# AerO2_Sheet1.net
KiCad netlist of a schematic drawn in Altium Designer
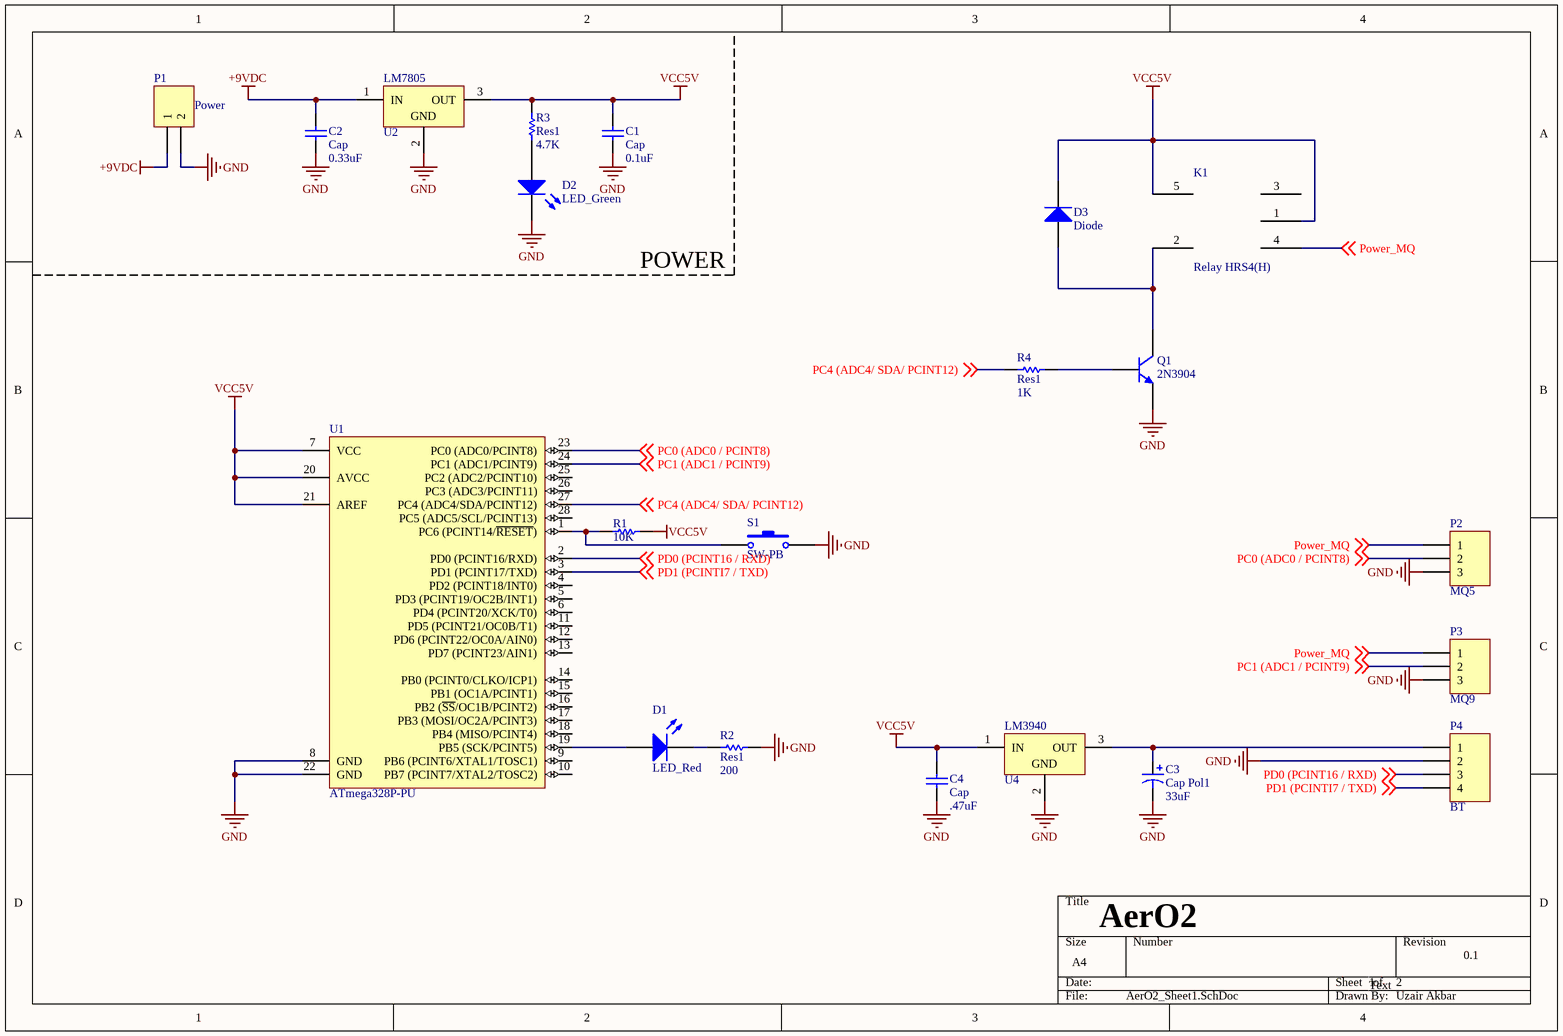
[diagram p0: AerO2_Sheet1.SchDoc]

(export (version "E")
  (design (tool "Eeschema 10.0.6"))
  (components
    (comp (ref "C1")
      (value "Cap")
      (footprint "RAD-0.1")
      (description "Capacitor")
      (fields (field (name "ALTIUM_VALUE") "0.1uF") (field (name "PUBLISHER") "Altium Limited"))
      (libsource (lib "Miscellaneous Devices") (part "Cap"))
    )
    (comp (ref "C2")
      (value "Cap")
      (footprint "RAD-0.1")
      (description "Capacitor")
      (fields (field (name "ALTIUM_VALUE") "0.33uF") (field (name "PUBLISHER") "Altium Limited"))
      (libsource (lib "Miscellaneous Devices") (part "Cap"))
    )
    (comp (ref "C3")
      (value "Cap Pol1")
      (footprint "RB5-10.5")
      (description "Polarized Capacitor (Radial)")
      (fields (field (name "ALTIUM_VALUE") "33uF") (field (name "PUBLISHER") "Altium Limited"))
      (libsource (lib "Miscellaneous Devices") (part "Cap Pol1"))
    )
    (comp (ref "C4")
      (value "Cap")
      (footprint "RAD-0.1")
      (description "Capacitor")
      (fields (field (name "ALTIUM_VALUE") ".47uF") (field (name "PUBLISHER") "Altium Limited"))
      (libsource (lib "Miscellaneous Devices") (part "Cap"))
    )
    (comp (ref "D1")
      (value "LED_Red")
      (footprint "LED-0")
      (description "Typical INFRARED GaAs LED")
      (fields (field (name "PUBLISHER") "Altium Limited"))
      (libsource (lib "Miscellaneous Devices") (part "LED0"))
    )
    (comp (ref "D2")
      (value "LED_Green")
      (footprint "LED-0")
      (description "Typical INFRARED GaAs LED")
      (fields (field (name "PUBLISHER") "Altium Limited"))
      (libsource (lib "Miscellaneous Devices") (part "LED0"))
    )
    (comp (ref "D3")
      (value "Diode")
      (footprint "DIODE-0.4")
      (description "Default Diode")
      (fields (field (name "PUBLISHER") "Altium Limited"))
      (libsource (lib "Miscellaneous Devices") (part "Diode"))
    )
    (comp (ref "K1")
      (value "Relay HRS4(H)")
      (footprint "Relay HRS4(H)")
      (libsource (lib "HRS4(H)_Relay") (part "Relay HRS4(H)"))
    )
    (comp (ref "P1")
      (value "Power")
      (footprint "HDR1X2")
      (description "Header, 2-Pin")
      (fields (field (name "PUBLISHER") "Altium Limited"))
      (libsource (lib "Miscellaneous Connectors") (part "Header 2"))
    )
    (comp (ref "P2")
      (value "MQ5")
      (footprint "HDR1X3")
      (description "Header, 3-Pin")
      (fields (field (name "PUBLISHER") "Altium Limited"))
      (libsource (lib "Miscellaneous Connectors") (part "Header 3"))
    )
    (comp (ref "P3")
      (value "MQ9")
      (footprint "HDR1X3")
      (description "Header, 3-Pin")
      (fields (field (name "PUBLISHER") "Altium Limited"))
      (libsource (lib "Miscellaneous Connectors") (part "Header 3"))
    )
    (comp (ref "P4")
      (value "BT")
      (footprint "HDR1X4")
      (description "Header, 4-Pin")
      (fields (field (name "PUBLISHER") "Altium Limited"))
      (libsource (lib "Miscellaneous Connectors") (part "Header 4"))
    )
    (comp (ref "Q1")
      (value "2N3904")
      (footprint "TO-92A")
      (description "NPN General Purpose Amplifier")
      (fields (field (name "PUBLISHER") "Altium Limited"))
      (libsource (lib "Miscellaneous Devices") (part "2N3904"))
    )
    (comp (ref "R1")
      (value "10K")
      (footprint "AXIAL-0.3")
      (description "Resistor")
      (fields (field (name "Comment") "Res1") (field (name "PUBLISHER") "Altium Limited"))
      (libsource (lib "Miscellaneous Devices") (part "Res1"))
    )
    (comp (ref "R2")
      (value "Res1")
      (footprint "AXIAL-0.3")
      (description "Resistor")
      (fields (field (name "ALTIUM_VALUE") "200") (field (name "PUBLISHER") "Altium Limited"))
      (libsource (lib "Miscellaneous Devices") (part "Res1"))
    )
    (comp (ref "R3")
      (value "Res1")
      (footprint "AXIAL-0.3")
      (description "Resistor")
      (fields (field (name "ALTIUM_VALUE") "4.7K") (field (name "PUBLISHER") "Altium Limited"))
      (libsource (lib "Miscellaneous Devices") (part "Res1"))
    )
    (comp (ref "R4")
      (value "Res1")
      (footprint "AXIAL-0.3")
      (description "Resistor")
      (fields (field (name "ALTIUM_VALUE") "1K") (field (name "PUBLISHER") "Altium Limited"))
      (libsource (lib "Miscellaneous Devices") (part "Res1"))
    )
    (comp (ref "S1")
      (value "SW-PB")
      (footprint "SPST-2")
      (description "Switch")
      (fields (field (name "PUBLISHER") "Altium Limited"))
      (libsource (lib "Miscellaneous Devices") (part "SW-PB"))
    )
    (comp (ref "U1")
      (value "ATmega328P-PU")
      (footprint "28P3")
      (fields (field (name "PUBLISHER") "Altium Limited"))
      (libsource (lib "Atmel Microcontroller 8-Bit megaAVR") (part "ATmega328P-PU"))
    )
    (comp (ref "U2")
      (value "LM7805")
      (footprint "TO-262-AA")
      (description "Positive-Voltage Regulator")
      (fields (field (name "PUBLISHER") "Altium Limited"))
      (libsource (lib "TI Power Mgt Voltage Regulator") (part "µA78M05CKC"))
    )
    (comp (ref "U4")
      (value "LM3940")
      (footprint "TO-262-AA")
      (description "Positive-Voltage Regulator")
      (fields (field (name "PUBLISHER") "Altium Limited"))
      (libsource (lib "TI Power Mgt Voltage Regulator") (part "µA78M05CKC"))
    )
  )
  (nets
    (net (code "1") (name "+9VDC") (class "Default")
      (node (ref "C2") (pin "1") (pinfunction "1_1") (pintype "passive"))
      (node (ref "P1") (pin "1") (pinfunction "1_1") (pintype "passive"))
      (node (ref "U2") (pin "1") (pinfunction "IN_1") (pintype "power_in"))
    )
    (net (code "2") (name "GND") (class "Default")
      (node (ref "C1") (pin "2") (pinfunction "2_2") (pintype "passive"))
      (node (ref "C2") (pin "2") (pinfunction "2_2") (pintype "passive"))
      (node (ref "C3") (pin "2") (pinfunction "2_2") (pintype "passive"))
      (node (ref "C4") (pin "1") (pinfunction "1_1") (pintype "passive"))
      (node (ref "D2") (pin "2") (pinfunction "K_2") (pintype "passive"))
      (node (ref "P1") (pin "2") (pinfunction "2_2") (pintype "passive"))
      (node (ref "P2") (pin "3") (pinfunction "3_3") (pintype "passive"))
      (node (ref "P3") (pin "3") (pinfunction "3_3") (pintype "passive"))
      (node (ref "P4") (pin "2") (pinfunction "2_2") (pintype "passive"))
      (node (ref "Q1") (pin "1") (pinfunction "E_1") (pintype "passive"))
      (node (ref "R2") (pin "2") (pinfunction "2_2") (pintype "passive"))
      (node (ref "S1") (pin "2") (pinfunction "2_2") (pintype "passive"))
      (node (ref "U1") (pin "22") (pinfunction "GND_22") (pintype "power_in"))
      (node (ref "U1") (pin "8") (pinfunction "GND_8") (pintype "power_in"))
      (node (ref "U2") (pin "2") (pinfunction "GND_2") (pintype "power_in"))
      (node (ref "U4") (pin "2") (pinfunction "GND_2") (pintype "power_in"))
    )
    (net (code "3") (name "Net-(D1-A)") (class "Default")
      (node (ref "D1") (pin "1") (pinfunction "A_1") (pintype "passive"))
      (node (ref "U1") (pin "19") (pinfunction "PB5_(SCK/PCINT5)_19") (pintype "bidirectional"))
    )
    (net (code "4") (name "Net-(D1-K)") (class "Default")
      (node (ref "D1") (pin "2") (pinfunction "K_2") (pintype "passive"))
      (node (ref "R2") (pin "1") (pinfunction "1_1") (pintype "passive"))
    )
    (net (code "5") (name "Net-(D2-A)") (class "Default")
      (node (ref "D2") (pin "1") (pinfunction "A_1") (pintype "passive"))
      (node (ref "R3") (pin "1") (pinfunction "1_1") (pintype "passive"))
    )
    (net (code "6") (name "Net-(D3-A)") (class "Default")
      (node (ref "D3") (pin "1") (pinfunction "A_1") (pintype "passive"))
      (node (ref "K1") (pin "2") (pintype "passive"))
      (node (ref "Q1") (pin "3") (pinfunction "C_3") (pintype "passive"))
    )
    (net (code "7") (name "Net-(Q1-B)") (class "Default")
      (node (ref "Q1") (pin "2") (pinfunction "B_2") (pintype "passive"))
      (node (ref "R4") (pin "2") (pinfunction "2_2") (pintype "passive"))
    )
    (net (code "8") (name "Net-(U1-PC6_(PCINT14{slash}~{RESET}))") (class "Default")
      (node (ref "R1") (pin "1") (pinfunction "1_1") (pintype "passive"))
      (node (ref "S1") (pin "1") (pinfunction "1_1") (pintype "passive"))
      (node (ref "U1") (pin "1") (pinfunction "PC6_(PCINT14/~{RESET})_1") (pintype "bidirectional"))
    )
    (net (code "9") (name "Net-(U4-OUT)") (class "Default")
      (node (ref "C3") (pin "1") (pinfunction "1_1") (pintype "passive"))
      (node (ref "P4") (pin "1") (pinfunction "1_1") (pintype "passive"))
      (node (ref "U4") (pin "3") (pinfunction "OUT_3") (pintype "power_in"))
    )
    (net (code "10") (name "PC0 (ADC0 {slash} PCINT8)") (class "Default")
      (node (ref "P2") (pin "2") (pinfunction "2_2") (pintype "passive"))
      (node (ref "U1") (pin "23") (pinfunction "PC0_(ADC0/PCINT8)_23") (pintype "bidirectional"))
    )
    (net (code "11") (name "PC1 (ADC1 {slash} PCINT9)") (class "Default")
      (node (ref "P3") (pin "2") (pinfunction "2_2") (pintype "passive"))
      (node (ref "U1") (pin "24") (pinfunction "PC1_(ADC1/PCINT9)_24") (pintype "bidirectional"))
    )
    (net (code "12") (name "PC4 (ADC4{slash} SDA{slash} PCINT12)") (class "Default")
      (node (ref "R4") (pin "1") (pinfunction "1_1") (pintype "passive"))
      (node (ref "U1") (pin "27") (pinfunction "PC4_(ADC4/SDA/PCINT12)_27") (pintype "bidirectional"))
    )
    (net (code "13") (name "PD0 (PCINT16 {slash} RXD)") (class "Default")
      (node (ref "P4") (pin "3") (pinfunction "3_3") (pintype "passive"))
      (node (ref "U1") (pin "2") (pinfunction "PD0_(PCINT16/RXD)_2") (pintype "bidirectional"))
    )
    (net (code "14") (name "PD1 (PCINTI7 {slash} TXD)") (class "Default")
      (node (ref "P4") (pin "4") (pinfunction "4_4") (pintype "passive"))
      (node (ref "U1") (pin "3") (pinfunction "PD1_(PCINT17/TXD)_3") (pintype "bidirectional"))
    )
    (net (code "15") (name "Power_MQ") (class "Default")
      (node (ref "K1") (pin "4") (pintype "passive"))
      (node (ref "P2") (pin "1") (pinfunction "1_1") (pintype "passive"))
      (node (ref "P3") (pin "1") (pinfunction "1_1") (pintype "passive"))
    )
    (net (code "16") (name "VCC5V") (class "Default")
      (node (ref "C1") (pin "1") (pinfunction "1_1") (pintype "passive"))
      (node (ref "C4") (pin "2") (pinfunction "2_2") (pintype "passive"))
      (node (ref "D3") (pin "2") (pinfunction "K_2") (pintype "passive"))
      (node (ref "K1") (pin "1") (pintype "passive"))
      (node (ref "K1") (pin "5") (pintype "passive"))
      (node (ref "R1") (pin "2") (pinfunction "2_2") (pintype "passive"))
      (node (ref "R3") (pin "2") (pinfunction "2_2") (pintype "passive"))
      (node (ref "U1") (pin "20") (pinfunction "AVCC_20") (pintype "power_in"))
      (node (ref "U1") (pin "21") (pinfunction "AREF_21") (pintype "power_in"))
      (node (ref "U1") (pin "7") (pinfunction "VCC_7") (pintype "power_in"))
      (node (ref "U2") (pin "3") (pinfunction "OUT_3") (pintype "power_in"))
      (node (ref "U4") (pin "1") (pinfunction "IN_1") (pintype "power_in"))
    )
    (net (code "17") (name "unconnected-(K1-Pad3)") (class "Default")
      (node (ref "K1") (pin "3") (pintype "passive"))
    )
    (net (code "18") (name "unconnected-(U1-PB0_(PCINT0{slash}CLKO{slash}ICP1)-Pad14)") (class "Default")
      (node (ref "U1") (pin "14") (pinfunction "PB0_(PCINT0/CLKO/ICP1)_14") (pintype "bidirectional"))
    )
    (net (code "19") (name "unconnected-(U1-PB1_(OC1A{slash}PCINT1)-Pad15)") (class "Default")
      (node (ref "U1") (pin "15") (pinfunction "PB1_(OC1A/PCINT1)_15") (pintype "bidirectional"))
    )
    (net (code "20") (name "unconnected-(U1-PB2_(~{SS}{slash}OC1B{slash}PCINT2)-Pad16)") (class "Default")
      (node (ref "U1") (pin "16") (pinfunction "PB2_(~{SS}/OC1B/PCINT2)_16") (pintype "bidirectional"))
    )
    (net (code "21") (name "unconnected-(U1-PB3_(MOSI{slash}OC2A{slash}PCINT3)-Pad17)") (class "Default")
      (node (ref "U1") (pin "17") (pinfunction "PB3_(MOSI/OC2A/PCINT3)_17") (pintype "bidirectional"))
    )
    (net (code "22") (name "unconnected-(U1-PB4_(MISO{slash}PCINT4)-Pad18)") (class "Default")
      (node (ref "U1") (pin "18") (pinfunction "PB4_(MISO/PCINT4)_18") (pintype "bidirectional"))
    )
    (net (code "23") (name "unconnected-(U1-PB6_(PCINT6{slash}XTAL1{slash}TOSC1)-Pad9)") (class "Default")
      (node (ref "U1") (pin "9") (pinfunction "PB6_(PCINT6/XTAL1/TOSC1)_9") (pintype "bidirectional"))
    )
    (net (code "24") (name "unconnected-(U1-PB7_(PCINT7{slash}XTAL2{slash}TOSC2)-Pad10)") (class "Default")
      (node (ref "U1") (pin "10") (pinfunction "PB7_(PCINT7/XTAL2/TOSC2)_10") (pintype "bidirectional"))
    )
    (net (code "25") (name "unconnected-(U1-PC2_(ADC2{slash}PCINT10)-Pad25)") (class "Default")
      (node (ref "U1") (pin "25") (pinfunction "PC2_(ADC2/PCINT10)_25") (pintype "bidirectional"))
    )
    (net (code "26") (name "unconnected-(U1-PC3_(ADC3{slash}PCINT11)-Pad26)") (class "Default")
      (node (ref "U1") (pin "26") (pinfunction "PC3_(ADC3/PCINT11)_26") (pintype "bidirectional"))
    )
    (net (code "27") (name "unconnected-(U1-PC5_(ADC5{slash}SCL{slash}PCINT13)-Pad28)") (class "Default")
      (node (ref "U1") (pin "28") (pinfunction "PC5_(ADC5/SCL/PCINT13)_28") (pintype "bidirectional"))
    )
    (net (code "28") (name "unconnected-(U1-PD2_(PCINT18{slash}INT0)-Pad4)") (class "Default")
      (node (ref "U1") (pin "4") (pinfunction "PD2_(PCINT18/INT0)_4") (pintype "bidirectional"))
    )
    (net (code "29") (name "unconnected-(U1-PD3_(PCINT19{slash}OC2B{slash}INT1)-Pad5)") (class "Default")
      (node (ref "U1") (pin "5") (pinfunction "PD3_(PCINT19/OC2B/INT1)_5") (pintype "bidirectional"))
    )
    (net (code "30") (name "unconnected-(U1-PD4_(PCINT20{slash}XCK{slash}T0)-Pad6)") (class "Default")
      (node (ref "U1") (pin "6") (pinfunction "PD4_(PCINT20/XCK/T0)_6") (pintype "bidirectional"))
    )
    (net (code "31") (name "unconnected-(U1-PD5_(PCINT21{slash}OC0B{slash}T1)-Pad11)") (class "Default")
      (node (ref "U1") (pin "11") (pinfunction "PD5_(PCINT21/OC0B/T1)_11") (pintype "bidirectional"))
    )
    (net (code "32") (name "unconnected-(U1-PD6_(PCINT22{slash}OC0A{slash}AIN0)-Pad12)") (class "Default")
      (node (ref "U1") (pin "12") (pinfunction "PD6_(PCINT22/OC0A/AIN0)_12") (pintype "bidirectional"))
    )
    (net (code "33") (name "unconnected-(U1-PD7_(PCINT23{slash}AIN1)-Pad13)") (class "Default")
      (node (ref "U1") (pin "13") (pinfunction "PD7_(PCINT23/AIN1)_13") (pintype "bidirectional"))
    )
  )
)
